# DB10011_Controller.net
KiCad netlist of a schematic drawn in Altium Designer
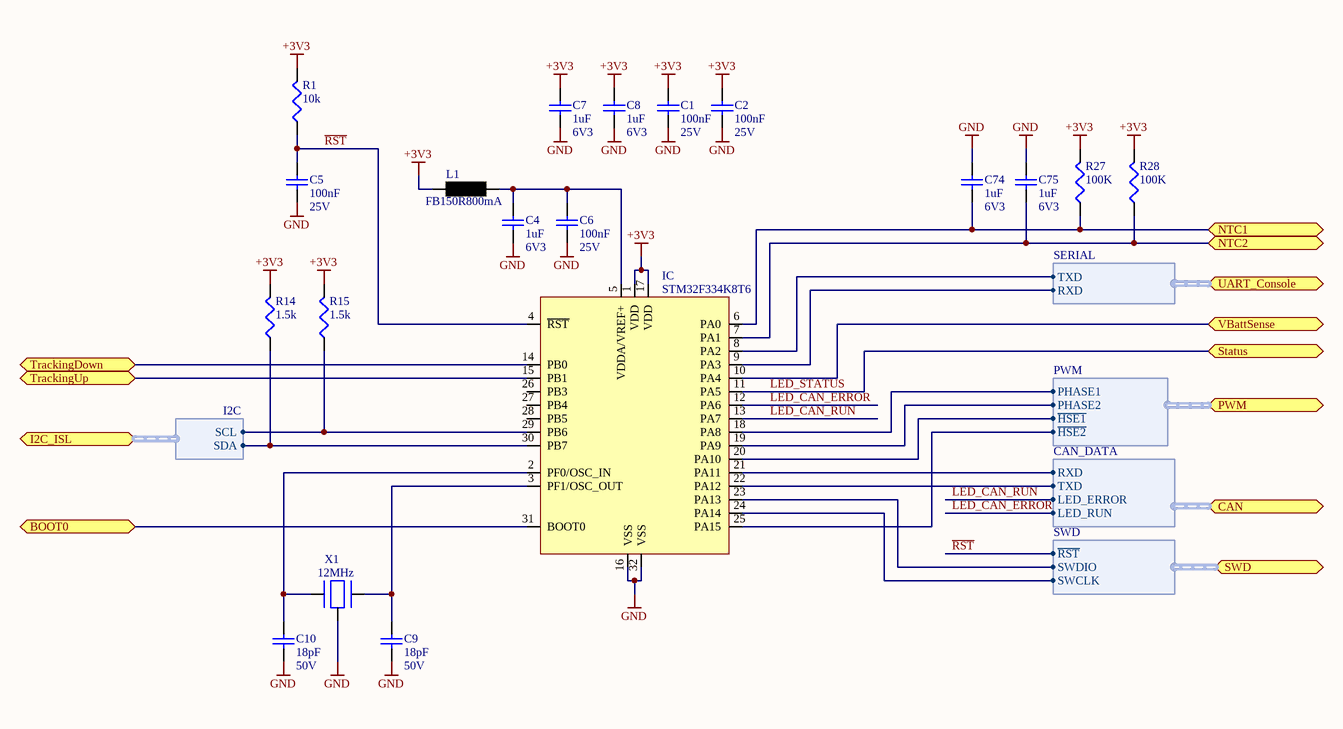
[diagram p0: DB10011_Controller.SchDoc]

(export (version "E")
  (design (tool "Eeschema 10.0.6"))
  (components
    (comp (ref "C1")
      (value "100nF")
      (footprint "C0402")
      (description "Capacitor, 100nF, 25V, X7R")
      (fields (field (name "VOLTAGE RATING") "25V"))
      (libsource (lib "AR_Capacitors_Ceramic") (part "100nF/0402/CER/25V"))
    )
    (comp (ref "C2")
      (value "100nF")
      (footprint "C0402")
      (description "Capacitor, 100nF, 25V, X7R")
      (fields (field (name "VOLTAGE RATING") "25V"))
      (libsource (lib "AR_Capacitors_Ceramic") (part "100nF/0402/CER/25V"))
    )
    (comp (ref "C4")
      (value "1uF")
      (footprint "C0402")
      (description "Capacitor, 1uF, 6.3V, X5R")
      (fields (field (name "VOLTAGE RATING") "6V3"))
      (libsource (lib "AR_Capacitors_Ceramic") (part "1uF/0402/CER/6.3V"))
    )
    (comp (ref "C5")
      (value "100nF")
      (footprint "C0402")
      (description "Capacitor, 100nF, 25V, X7R")
      (fields (field (name "VOLTAGE RATING") "25V"))
      (libsource (lib "AR_Capacitors_Ceramic") (part "100nF/0402/CER/25V"))
    )
    (comp (ref "C6")
      (value "100nF")
      (footprint "C0402")
      (description "Capacitor, 100nF, 25V, X7R")
      (fields (field (name "VOLTAGE RATING") "25V"))
      (libsource (lib "AR_Capacitors_Ceramic") (part "100nF/0402/CER/25V"))
    )
    (comp (ref "C7")
      (value "1uF")
      (footprint "C0402")
      (description "Capacitor, 1uF, 6.3V, X5R")
      (fields (field (name "VOLTAGE RATING") "6V3"))
      (libsource (lib "AR_Capacitors_Ceramic") (part "1uF/0402/CER/6.3V"))
    )
    (comp (ref "C8")
      (value "1uF")
      (footprint "C0402")
      (description "Capacitor, 1uF, 6.3V, X5R")
      (fields (field (name "VOLTAGE RATING") "6V3"))
      (libsource (lib "AR_Capacitors_Ceramic") (part "1uF/0402/CER/6.3V"))
    )
    (comp (ref "C9")
      (value "18pF")
      (footprint "C0402")
      (description "Capacitor, 18pF, 50V, NP0")
      (fields (field (name "VOLTAGE RATING") "50V"))
      (libsource (lib "AR_Capacitors_Ceramic") (part "18pF/0402/CER/50V"))
    )
    (comp (ref "C10")
      (value "18pF")
      (footprint "C0402")
      (description "Capacitor, 18pF, 50V, NP0")
      (fields (field (name "VOLTAGE RATING") "50V"))
      (libsource (lib "AR_Capacitors_Ceramic") (part "18pF/0402/CER/50V"))
    )
    (comp (ref "C74")
      (value "1uF")
      (footprint "C0402")
      (description "Capacitor, 1uF, 6.3V, X5R")
      (fields (field (name "VOLTAGE RATING") "6V3"))
      (libsource (lib "AR_Capacitors_Ceramic") (part "1uF/0402/CER/6.3V"))
    )
    (comp (ref "C75")
      (value "1uF")
      (footprint "C0402")
      (description "Capacitor, 1uF, 6.3V, X5R")
      (fields (field (name "VOLTAGE RATING") "6V3"))
      (libsource (lib "AR_Capacitors_Ceramic") (part "1uF/0402/CER/6.3V"))
    )
    (comp (ref "IC")
      (value "STM32F334K8T6")
      (footprint "LQFP32")
      (description "MCU, 32BIT CORTEX-M3, 72MHz, HRTIM")
      (libsource (lib "AR_Microcontrollers") (part "STM32F334K8T6"))
    )
    (comp (ref "L1")
      (value "FB150R800mA")
      (footprint "0805")
      (description "Ferrite, 150R, 0.8Adc, 100MHz")
      (libsource (lib "AR_Inductors") (part "LI0805H151R"))
    )
    (comp (ref "R1")
      (value "10k")
      (footprint "0402")
      (description "Resistor, 10k, 0.1%, 0.0625W, 50V, 100PPM, 0402")
      (libsource (lib "AR_Resistors_SMD") (part "10k/0402/0063W/50V"))
    )
    (comp (ref "R14")
      (value "1.5k")
      (footprint "0402")
      (description "Resistor, 1.5k, 0.1%, 0.0625W, 50V, 100PPM, 0402")
      (libsource (lib "AR_Resistors_SMD") (part "1.5k/0402/0063W/50V"))
    )
    (comp (ref "R15")
      (value "1.5k")
      (footprint "0402")
      (description "Resistor, 1.5k, 0.1%, 0.0625W, 50V, 100PPM, 0402")
      (libsource (lib "AR_Resistors_SMD") (part "1.5k/0402/0063W/50V"))
    )
    (comp (ref "R27")
      (value "100K")
      (footprint "0402")
      (description "Resistor, 100k, 0.1%, 0.0625W, 50V, 100PPM, 0402")
      (libsource (lib "AR_Resistors_SMD") (part "100k/0402/0063W/50V"))
    )
    (comp (ref "R28")
      (value "100K")
      (footprint "0402")
      (description "Resistor, 100k, 0.1%, 0.0625W, 50V, 100PPM, 0402")
      (libsource (lib "AR_Resistors_SMD") (part "100k/0402/0063W/50V"))
    )
    (comp (ref "X1")
      (value "12MHz")
      (footprint "7M")
      (description "CRYSTAL, 12MHz,18PF CL, 3.2X2.5MM SMT")
      (libsource (lib "AR_Crystals") (part "7M-12.000MAAJ-T"))
    )
  )
  (nets
    (net (code "6") (name "+3V3") (class "Default")
      (node (ref "C1") (pin "2") (pinfunction "2_2") (pintype "passive"))
      (node (ref "C2") (pin "2") (pinfunction "2_2") (pintype "passive"))
      (node (ref "C7") (pin "2") (pinfunction "2_2") (pintype "passive"))
      (node (ref "C8") (pin "2") (pinfunction "2_2") (pintype "passive"))
      (node (ref "IC") (pin "1") (pinfunction "VDD_1") (pintype "passive"))
      (node (ref "IC") (pin "17") (pinfunction "VDD_17") (pintype "passive"))
      (node (ref "L1") (pin "1") (pinfunction "1_1") (pintype "passive"))
      (node (ref "R1") (pin "2") (pinfunction "2_2") (pintype "passive"))
      (node (ref "R14") (pin "2") (pinfunction "2_2") (pintype "passive"))
      (node (ref "R15") (pin "2") (pinfunction "2_2") (pintype "passive"))
      (node (ref "R27") (pin "2") (pinfunction "2_2") (pintype "passive"))
      (node (ref "R28") (pin "2") (pinfunction "2_2") (pintype "passive"))
    )
    (net (code "7") (name "/BOOT0") (class "Default")
      (node (ref "IC") (pin "31") (pinfunction "BOOT0_31") (pintype "passive"))
    )
    (net (code "8") (name "/LED_CAN_ERROR") (class "Default")
      (node (ref "IC") (pin "12") (pinfunction "PA6_12") (pintype "passive"))
    )
    (net (code "9") (name "/LED_CAN_RUN") (class "Default")
      (node (ref "IC") (pin "13") (pinfunction "PA7_13") (pintype "passive"))
    )
    (net (code "10") (name "/LED_STATUS") (class "Default")
      (node (ref "IC") (pin "11") (pinfunction "PA5_11") (pintype "passive"))
    )
    (net (code "11") (name "/NTC1") (class "Default")
      (node (ref "C74") (pin "1") (pinfunction "1_1") (pintype "passive"))
      (node (ref "IC") (pin "6") (pinfunction "PA0_6") (pintype "passive"))
      (node (ref "R27") (pin "1") (pinfunction "1_1") (pintype "passive"))
    )
    (net (code "12") (name "/NTC2") (class "Default")
      (node (ref "C75") (pin "1") (pinfunction "1_1") (pintype "passive"))
      (node (ref "IC") (pin "7") (pinfunction "PA1_7") (pintype "passive"))
      (node (ref "R28") (pin "1") (pinfunction "1_1") (pintype "passive"))
    )
    (net (code "13") (name "/PHASE1") (class "Default")
      (node (ref "IC") (pin "18") (pinfunction "PA8_18") (pintype "passive"))
    )
    (net (code "14") (name "/PHASE2") (class "Default")
      (node (ref "IC") (pin "19") (pinfunction "PA9_19") (pintype "passive"))
    )
    (net (code "15") (name "/SCL") (class "Default")
      (node (ref "IC") (pin "29") (pinfunction "PB6_29") (pintype "passive"))
      (node (ref "R15") (pin "1") (pinfunction "1_1") (pintype "passive"))
    )
    (net (code "16") (name "/SDA") (class "Default")
      (node (ref "IC") (pin "30") (pinfunction "PB7_30") (pintype "passive"))
      (node (ref "R14") (pin "1") (pinfunction "1_1") (pintype "passive"))
    )
    (net (code "17") (name "/SWCLK") (class "Default")
      (node (ref "IC") (pin "24") (pinfunction "PA14_24") (pintype "passive"))
    )
    (net (code "18") (name "/SWDIO") (class "Default")
      (node (ref "IC") (pin "23") (pinfunction "PA13_23") (pintype "passive"))
    )
    (net (code "19") (name "/TrackingDown") (class "Default")
      (node (ref "IC") (pin "14") (pinfunction "PB0_14") (pintype "passive"))
    )
    (net (code "20") (name "/TrackingUp") (class "Default")
      (node (ref "IC") (pin "15") (pinfunction "PB1_15") (pintype "passive"))
    )
    (net (code "21") (name "/VBattSense") (class "Default")
      (node (ref "IC") (pin "10") (pinfunction "PA4_10") (pintype "passive"))
    )
    (net (code "27") (name "/~{HSE1}") (class "Default")
      (node (ref "IC") (pin "20") (pinfunction "PA10_20") (pintype "passive"))
    )
    (net (code "28") (name "/~{HSE2}") (class "Default")
      (node (ref "IC") (pin "25") (pinfunction "PA15_25") (pintype "passive"))
    )
    (net (code "29") (name "/~{RST}") (class "Default")
      (node (ref "C5") (pin "2") (pinfunction "2_2") (pintype "passive"))
      (node (ref "IC") (pin "4") (pinfunction "~{RST}_4") (pintype "passive"))
      (node (ref "R1") (pin "1") (pinfunction "1_1") (pintype "passive"))
    )
    (net (code "30") (name "GND") (class "Default")
      (node (ref "C1") (pin "1") (pinfunction "1_1") (pintype "passive"))
      (node (ref "C10") (pin "1") (pinfunction "1_1") (pintype "passive"))
      (node (ref "C2") (pin "1") (pinfunction "1_1") (pintype "passive"))
      (node (ref "C4") (pin "1") (pinfunction "1_1") (pintype "passive"))
      (node (ref "C5") (pin "1") (pinfunction "1_1") (pintype "passive"))
      (node (ref "C6") (pin "1") (pinfunction "1_1") (pintype "passive"))
      (node (ref "C7") (pin "1") (pinfunction "1_1") (pintype "passive"))
      (node (ref "C74") (pin "2") (pinfunction "2_2") (pintype "passive"))
      (node (ref "C75") (pin "2") (pinfunction "2_2") (pintype "passive"))
      (node (ref "C8") (pin "1") (pinfunction "1_1") (pintype "passive"))
      (node (ref "C9") (pin "1") (pinfunction "1_1") (pintype "passive"))
      (node (ref "IC") (pin "16") (pinfunction "VSS_16") (pintype "passive"))
      (node (ref "IC") (pin "32") (pinfunction "VSS_32") (pintype "passive"))
      (node (ref "X1") (pin "0") (pinfunction "0_0") (pintype "power_in"))
    )
    (net (code "31") (name "Net-(IC-PF0{slash}OSC_IN)") (class "Default")
      (node (ref "C10") (pin "2") (pinfunction "2_2") (pintype "passive"))
      (node (ref "IC") (pin "2") (pinfunction "PF0/OSC_IN_2") (pintype "passive"))
      (node (ref "X1") (pin "1") (pinfunction "1_1") (pintype "passive"))
    )
    (net (code "32") (name "Net-(IC-PF1{slash}OSC_OUT)") (class "Default")
      (node (ref "C9") (pin "2") (pinfunction "2_2") (pintype "passive"))
      (node (ref "IC") (pin "3") (pinfunction "PF1/OSC_OUT_3") (pintype "passive"))
      (node (ref "X1") (pin "2") (pinfunction "2_2") (pintype "passive"))
    )
    (net (code "33") (name "Net-(IC-VDDA{slash}VREF+)") (class "Default")
      (node (ref "C4") (pin "2") (pinfunction "2_2") (pintype "passive"))
      (node (ref "C6") (pin "2") (pinfunction "2_2") (pintype "passive"))
      (node (ref "IC") (pin "5") (pinfunction "VDDA/VREF+_5") (pintype "passive"))
      (node (ref "L1") (pin "2") (pinfunction "2_2") (pintype "passive"))
    )
    (net (code "34") (name "unconnected-(IC-PA2-Pad8)") (class "Default")
      (node (ref "IC") (pin "8") (pinfunction "PA2_8") (pintype "passive"))
    )
    (net (code "35") (name "unconnected-(IC-PA3-Pad9)") (class "Default")
      (node (ref "IC") (pin "9") (pinfunction "PA3_9") (pintype "passive"))
    )
    (net (code "36") (name "unconnected-(IC-PA11-Pad21)") (class "Default")
      (node (ref "IC") (pin "21") (pinfunction "PA11_21") (pintype "passive"))
    )
    (net (code "37") (name "unconnected-(IC-PA12-Pad22)") (class "Default")
      (node (ref "IC") (pin "22") (pinfunction "PA12_22") (pintype "passive"))
    )
    (net (code "38") (name "unconnected-(IC-PB3-Pad26)") (class "Default")
      (node (ref "IC") (pin "26") (pinfunction "PB3_26") (pintype "passive"))
    )
    (net (code "39") (name "unconnected-(IC-PB4-Pad27)") (class "Default")
      (node (ref "IC") (pin "27") (pinfunction "PB4_27") (pintype "passive"))
    )
    (net (code "40") (name "unconnected-(IC-PB5-Pad28)") (class "Default")
      (node (ref "IC") (pin "28") (pinfunction "PB5_28") (pintype "passive"))
    )
  )
)
